# miniFlyportProgrammer.net
KiCad netlist of a schematic drawn in EAGLE
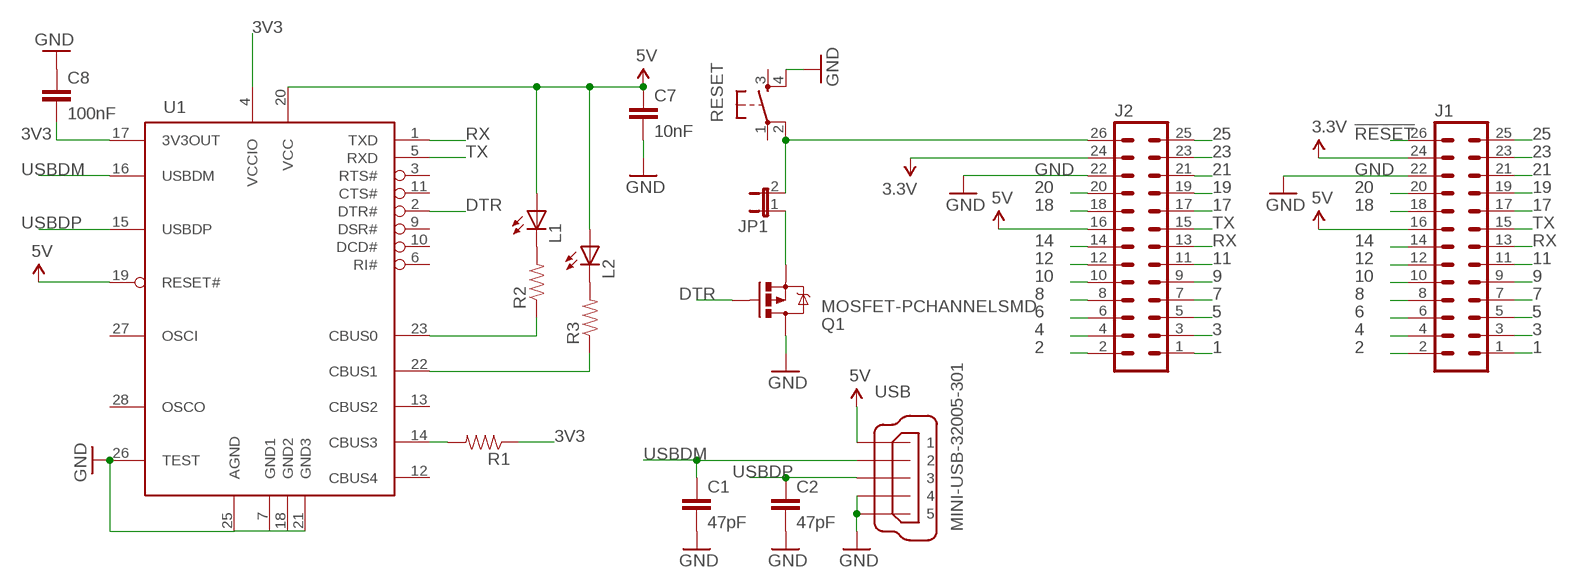
[diagram p0: schematic, sheet 1]

(export (version "E")
  (design (tool "Eeschema 10.0.6"))
  (components
    (comp (ref "C1")
      (value "47pF")
      (footprint "eagle-import:C0603")
      (libsource (lib "eagle-import") (part "C-EUC0603"))
    )
    (comp (ref "C2")
      (value "47pF")
      (footprint "eagle-import:C0603")
      (libsource (lib "eagle-import") (part "C-EUC0603"))
    )
    (comp (ref "C7")
      (value "10nF")
      (footprint "eagle-import:C0603")
      (libsource (lib "eagle-import") (part "C-EUC0603"))
    )
    (comp (ref "C8")
      (value "100nF")
      (footprint "eagle-import:C0603")
      (libsource (lib "eagle-import") (part "C-EUC0603"))
    )
    (comp (ref "J1")
      (value "MA13-2")
      (footprint "eagle-import:MA13-2")
      (libsource (lib "eagle-import") (part "MA13-2"))
    )
    (comp (ref "J2")
      (value "MA13-2")
      (footprint "eagle-import:MA13-2")
      (libsource (lib "eagle-import") (part "MA13-2"))
    )
    (comp (ref "JP1")
      (value "JUMPER-2PTH")
      (footprint "eagle-import:1X02")
      (libsource (lib "eagle-import") (part "JUMPER-2PTH"))
    )
    (comp (ref "L1")
      (value "LED0603")
      (footprint "eagle-import:LED-0603")
      (libsource (lib "eagle-import") (part "LED0603"))
    )
    (comp (ref "L2")
      (value "LED0603")
      (footprint "eagle-import:LED-0603")
      (libsource (lib "eagle-import") (part "LED0603"))
    )
    (comp (ref "Q1")
      (value "MOSFET-PCHANNELSMD")
      (footprint "eagle-import:SOT23-3")
      (libsource (lib "eagle-import") (part "MOSFET-PCHANNELSMD"))
    )
    (comp (ref "R1")
      (value "RESISTOR0603-RES")
      (footprint "eagle-import:0603-RES")
      (libsource (lib "eagle-import") (part "RESISTOR0603-RES"))
    )
    (comp (ref "R2")
      (value "RESISTOR0603-RES")
      (footprint "eagle-import:0603-RES")
      (libsource (lib "eagle-import") (part "RESISTOR0603-RES"))
    )
    (comp (ref "R3")
      (value "RESISTOR0603-RES")
      (footprint "eagle-import:0603-RES")
      (libsource (lib "eagle-import") (part "RESISTOR0603-RES"))
    )
    (comp (ref "RESET")
      (value "TAC_SWITCHSMD")
      (footprint "eagle-import:TACTILE_SWITCH_SMD")
      (libsource (lib "eagle-import") (part "TAC_SWITCHSMD"))
    )
    (comp (ref "U1")
      (value "FT232RL")
      (footprint "eagle-import:SSOP28DB")
      (libsource (lib "eagle-import") (part "FT232RL"))
    )
    (comp (ref "USB")
      (value "MINI-USB-32005-301")
      (footprint "eagle-import:32005-301")
      (libsource (lib "eagle-import") (part "MINI-USB-32005-301"))
    )
  )
  (nets
    (net (code "1") (name "/1") (class "Default")
      (node (ref "J1") (pin "1") (pinfunction "1_1") (pintype "passive"))
      (node (ref "J2") (pin "1") (pinfunction "1_1") (pintype "passive"))
    )
    (net (code "2") (name "/2") (class "Default")
      (node (ref "J1") (pin "2") (pinfunction "2_2") (pintype "passive"))
      (node (ref "J2") (pin "2") (pinfunction "2_2") (pintype "passive"))
    )
    (net (code "3") (name "/3") (class "Default")
      (node (ref "J1") (pin "3") (pinfunction "3_3") (pintype "passive"))
      (node (ref "J2") (pin "3") (pinfunction "3_3") (pintype "passive"))
    )
    (net (code "4") (name "/3V3") (class "Default")
      (node (ref "C8") (pin "2") (pinfunction "2_2") (pintype "passive"))
      (node (ref "R1") (pin "1") (pinfunction "1_1") (pintype "passive"))
      (node (ref "U1") (pin "17") (pinfunction "3V3OUT_17") (pintype "output"))
      (node (ref "U1") (pin "4") (pinfunction "VCCIO_4") (pintype "power_in"))
    )
    (net (code "5") (name "/4") (class "Default")
      (node (ref "J1") (pin "4") (pinfunction "4_4") (pintype "passive"))
      (node (ref "J2") (pin "4") (pinfunction "4_4") (pintype "passive"))
    )
    (net (code "6") (name "/5") (class "Default")
      (node (ref "J1") (pin "5") (pinfunction "5_5") (pintype "passive"))
      (node (ref "J2") (pin "5") (pinfunction "5_5") (pintype "passive"))
    )
    (net (code "7") (name "/6") (class "Default")
      (node (ref "J1") (pin "6") (pinfunction "6_6") (pintype "passive"))
      (node (ref "J2") (pin "6") (pinfunction "6_6") (pintype "passive"))
    )
    (net (code "8") (name "/7") (class "Default")
      (node (ref "J1") (pin "7") (pinfunction "7_7") (pintype "passive"))
      (node (ref "J2") (pin "7") (pinfunction "7_7") (pintype "passive"))
    )
    (net (code "9") (name "/8") (class "Default")
      (node (ref "J1") (pin "8") (pinfunction "8_8") (pintype "passive"))
      (node (ref "J2") (pin "8") (pinfunction "8_8") (pintype "passive"))
    )
    (net (code "10") (name "/9") (class "Default")
      (node (ref "J1") (pin "9") (pinfunction "9_9") (pintype "passive"))
      (node (ref "J2") (pin "9") (pinfunction "9_9") (pintype "passive"))
    )
    (net (code "11") (name "/10") (class "Default")
      (node (ref "J1") (pin "10") (pinfunction "10_10") (pintype "passive"))
      (node (ref "J2") (pin "10") (pinfunction "10_10") (pintype "passive"))
    )
    (net (code "12") (name "/11") (class "Default")
      (node (ref "J1") (pin "11") (pinfunction "11_11") (pintype "passive"))
      (node (ref "J2") (pin "11") (pinfunction "11_11") (pintype "passive"))
    )
    (net (code "13") (name "/12") (class "Default")
      (node (ref "J1") (pin "12") (pinfunction "12_12") (pintype "passive"))
      (node (ref "J2") (pin "12") (pinfunction "12_12") (pintype "passive"))
    )
    (net (code "14") (name "/14") (class "Default")
      (node (ref "J1") (pin "14") (pinfunction "14_14") (pintype "passive"))
      (node (ref "J2") (pin "14") (pinfunction "14_14") (pintype "passive"))
    )
    (net (code "15") (name "/17") (class "Default")
      (node (ref "J1") (pin "17") (pinfunction "17_17") (pintype "passive"))
      (node (ref "J2") (pin "17") (pinfunction "17_17") (pintype "passive"))
    )
    (net (code "16") (name "/18") (class "Default")
      (node (ref "J1") (pin "18") (pinfunction "18_18") (pintype "passive"))
      (node (ref "J2") (pin "18") (pinfunction "18_18") (pintype "passive"))
    )
    (net (code "17") (name "/19") (class "Default")
      (node (ref "J1") (pin "19") (pinfunction "19_19") (pintype "passive"))
      (node (ref "J2") (pin "19") (pinfunction "19_19") (pintype "passive"))
    )
    (net (code "18") (name "/20") (class "Default")
      (node (ref "J1") (pin "20") (pinfunction "20_20") (pintype "passive"))
      (node (ref "J2") (pin "20") (pinfunction "20_20") (pintype "passive"))
    )
    (net (code "19") (name "/21") (class "Default")
      (node (ref "J1") (pin "21") (pinfunction "21_21") (pintype "passive"))
      (node (ref "J2") (pin "21") (pinfunction "21_21") (pintype "passive"))
    )
    (net (code "20") (name "/23") (class "Default")
      (node (ref "J1") (pin "23") (pinfunction "23_23") (pintype "passive"))
      (node (ref "J2") (pin "23") (pinfunction "23_23") (pintype "passive"))
    )
    (net (code "21") (name "/25") (class "Default")
      (node (ref "J1") (pin "25") (pinfunction "25_25") (pintype "passive"))
      (node (ref "J2") (pin "25") (pinfunction "25_25") (pintype "passive"))
    )
    (net (code "22") (name "/DTR") (class "Default")
      (node (ref "Q1") (pin "1") (pinfunction "G_1") (pintype "passive"))
      (node (ref "U1") (pin "2") (pinfunction "DTR#_2") (pintype "output"))
    )
    (net (code "23") (name "/RX") (class "Default")
      (node (ref "J1") (pin "13") (pinfunction "13_13") (pintype "passive"))
      (node (ref "J2") (pin "13") (pinfunction "13_13") (pintype "passive"))
      (node (ref "U1") (pin "1") (pinfunction "TXD_1") (pintype "output"))
    )
    (net (code "24") (name "/TX") (class "Default")
      (node (ref "J1") (pin "15") (pinfunction "15_15") (pintype "passive"))
      (node (ref "J2") (pin "15") (pinfunction "15_15") (pintype "passive"))
      (node (ref "U1") (pin "5") (pinfunction "RXD_5") (pintype "input"))
    )
    (net (code "25") (name "/USBDM") (class "Default")
      (node (ref "C1") (pin "1") (pinfunction "1_1") (pintype "passive"))
      (node (ref "U1") (pin "16") (pinfunction "USBDM_16") (pintype "bidirectional"))
      (node (ref "USB") (pin "2") (pinfunction "2_2") (pintype "passive"))
    )
    (net (code "26") (name "/USBDP") (class "Default")
      (node (ref "C2") (pin "1") (pinfunction "1_1") (pintype "passive"))
      (node (ref "U1") (pin "15") (pinfunction "USBDP_15") (pintype "bidirectional"))
      (node (ref "USB") (pin "3") (pinfunction "3_3") (pintype "passive"))
    )
    (net (code "27") (name "/~{RESET}") (class "Default")
      (node (ref "J1") (pin "26") (pinfunction "26_26") (pintype "passive"))
      (node (ref "J2") (pin "26") (pinfunction "26_26") (pintype "passive"))
      (node (ref "JP1") (pin "2") (pinfunction "2_2") (pintype "passive"))
      (node (ref "RESET") (pin "2") (pinfunction "2_2") (pintype "passive"))
    )
    (net (code "28") (name "3.3V") (class "Default")
      (node (ref "J1") (pin "24") (pinfunction "24_24") (pintype "passive"))
      (node (ref "J2") (pin "24") (pinfunction "24_24") (pintype "passive"))
    )
    (net (code "29") (name "5V") (class "Default")
      (node (ref "C7") (pin "1") (pinfunction "1_1") (pintype "passive"))
      (node (ref "J1") (pin "16") (pinfunction "16_16") (pintype "passive"))
      (node (ref "J2") (pin "16") (pinfunction "16_16") (pintype "passive"))
      (node (ref "L1") (pin "A") (pinfunction "A_A") (pintype "passive"))
      (node (ref "L2") (pin "A") (pinfunction "A_A") (pintype "passive"))
      (node (ref "U1") (pin "19") (pinfunction "RESET#_19") (pintype "input"))
      (node (ref "U1") (pin "20") (pinfunction "VCC_20") (pintype "power_in"))
      (node (ref "USB") (pin "1") (pinfunction "1_1") (pintype "passive"))
    )
    (net (code "30") (name "GND") (class "Default")
      (node (ref "C1") (pin "2") (pinfunction "2_2") (pintype "passive"))
      (node (ref "C2") (pin "2") (pinfunction "2_2") (pintype "passive"))
      (node (ref "C7") (pin "2") (pinfunction "2_2") (pintype "passive"))
      (node (ref "C8") (pin "1") (pinfunction "1_1") (pintype "passive"))
      (node (ref "J1") (pin "22") (pinfunction "22_22") (pintype "passive"))
      (node (ref "J2") (pin "22") (pinfunction "22_22") (pintype "passive"))
      (node (ref "Q1") (pin "3") (pinfunction "D_3") (pintype "passive"))
      (node (ref "RESET") (pin "4") (pinfunction "4_4") (pintype "passive"))
      (node (ref "U1") (pin "18") (pinfunction "GND2_18") (pintype "power_in"))
      (node (ref "U1") (pin "21") (pinfunction "GND3_21") (pintype "power_in"))
      (node (ref "U1") (pin "25") (pinfunction "AGND_25") (pintype "power_in"))
      (node (ref "U1") (pin "26") (pinfunction "TEST_26") (pintype "input"))
      (node (ref "U1") (pin "7") (pinfunction "GND1_7") (pintype "power_in"))
      (node (ref "USB") (pin "4") (pinfunction "4_4") (pintype "passive"))
      (node (ref "USB") (pin "5") (pinfunction "5_5") (pintype "passive"))
    )
    (net (code "31") (name "Net-(L1-PadC)") (class "Default")
      (node (ref "L1") (pin "C") (pinfunction "C_C") (pintype "passive"))
      (node (ref "R2") (pin "2") (pinfunction "2_2") (pintype "passive"))
    )
    (net (code "32") (name "Net-(L2-PadC)") (class "Default")
      (node (ref "L2") (pin "C") (pinfunction "C_C") (pintype "passive"))
      (node (ref "R3") (pin "2") (pinfunction "2_2") (pintype "passive"))
    )
    (net (code "33") (name "Net-(Q1-S)") (class "Default")
      (node (ref "JP1") (pin "1") (pinfunction "1_1") (pintype "passive"))
      (node (ref "Q1") (pin "2") (pinfunction "S_2") (pintype "passive"))
    )
    (net (code "34") (name "Net-(U1-CBUS0)") (class "Default")
      (node (ref "R2") (pin "1") (pinfunction "1_1") (pintype "passive"))
      (node (ref "U1") (pin "23") (pinfunction "CBUS0_23") (pintype "bidirectional"))
    )
    (net (code "35") (name "Net-(U1-CBUS1)") (class "Default")
      (node (ref "R3") (pin "1") (pinfunction "1_1") (pintype "passive"))
      (node (ref "U1") (pin "22") (pinfunction "CBUS1_22") (pintype "bidirectional"))
    )
    (net (code "36") (name "Net-(U1-CBUS3)") (class "Default")
      (node (ref "R1") (pin "2") (pinfunction "2_2") (pintype "passive"))
      (node (ref "U1") (pin "14") (pinfunction "CBUS3_14") (pintype "bidirectional"))
    )
    (net (code "37") (name "unconnected-(RESET-Pad1)") (class "Default")
      (node (ref "RESET") (pin "1") (pinfunction "1_1") (pintype "passive"))
    )
    (net (code "38") (name "unconnected-(RESET-Pad3)") (class "Default")
      (node (ref "RESET") (pin "3") (pinfunction "3_3") (pintype "passive"))
    )
    (net (code "39") (name "unconnected-(U1-CBUS2-Pad13)") (class "Default")
      (node (ref "U1") (pin "13") (pinfunction "CBUS2_13") (pintype "bidirectional"))
    )
    (net (code "40") (name "unconnected-(U1-CBUS4-Pad12)") (class "Default")
      (node (ref "U1") (pin "12") (pinfunction "CBUS4_12") (pintype "bidirectional"))
    )
    (net (code "41") (name "unconnected-(U1-CTS#-Pad11)") (class "Default")
      (node (ref "U1") (pin "11") (pinfunction "CTS#_11") (pintype "input"))
    )
    (net (code "42") (name "unconnected-(U1-DCD#-Pad10)") (class "Default")
      (node (ref "U1") (pin "10") (pinfunction "DCD#_10") (pintype "input"))
    )
    (net (code "43") (name "unconnected-(U1-DSR#-Pad9)") (class "Default")
      (node (ref "U1") (pin "9") (pinfunction "DSR#_9") (pintype "input"))
    )
    (net (code "44") (name "unconnected-(U1-OSCI-Pad27)") (class "Default")
      (node (ref "U1") (pin "27") (pinfunction "OSCI_27") (pintype "input"))
    )
    (net (code "45") (name "unconnected-(U1-OSCO-Pad28)") (class "Default")
      (node (ref "U1") (pin "28") (pinfunction "OSCO_28") (pintype "output"))
    )
    (net (code "46") (name "unconnected-(U1-RI#-Pad6)") (class "Default")
      (node (ref "U1") (pin "6") (pinfunction "RI#_6") (pintype "input"))
    )
    (net (code "47") (name "unconnected-(U1-RTS#-Pad3)") (class "Default")
      (node (ref "U1") (pin "3") (pinfunction "RTS#_3") (pintype "output"))
    )
  )
)
